# digital-psu.net
KiCad netlist of a schematic drawn in EAGLE
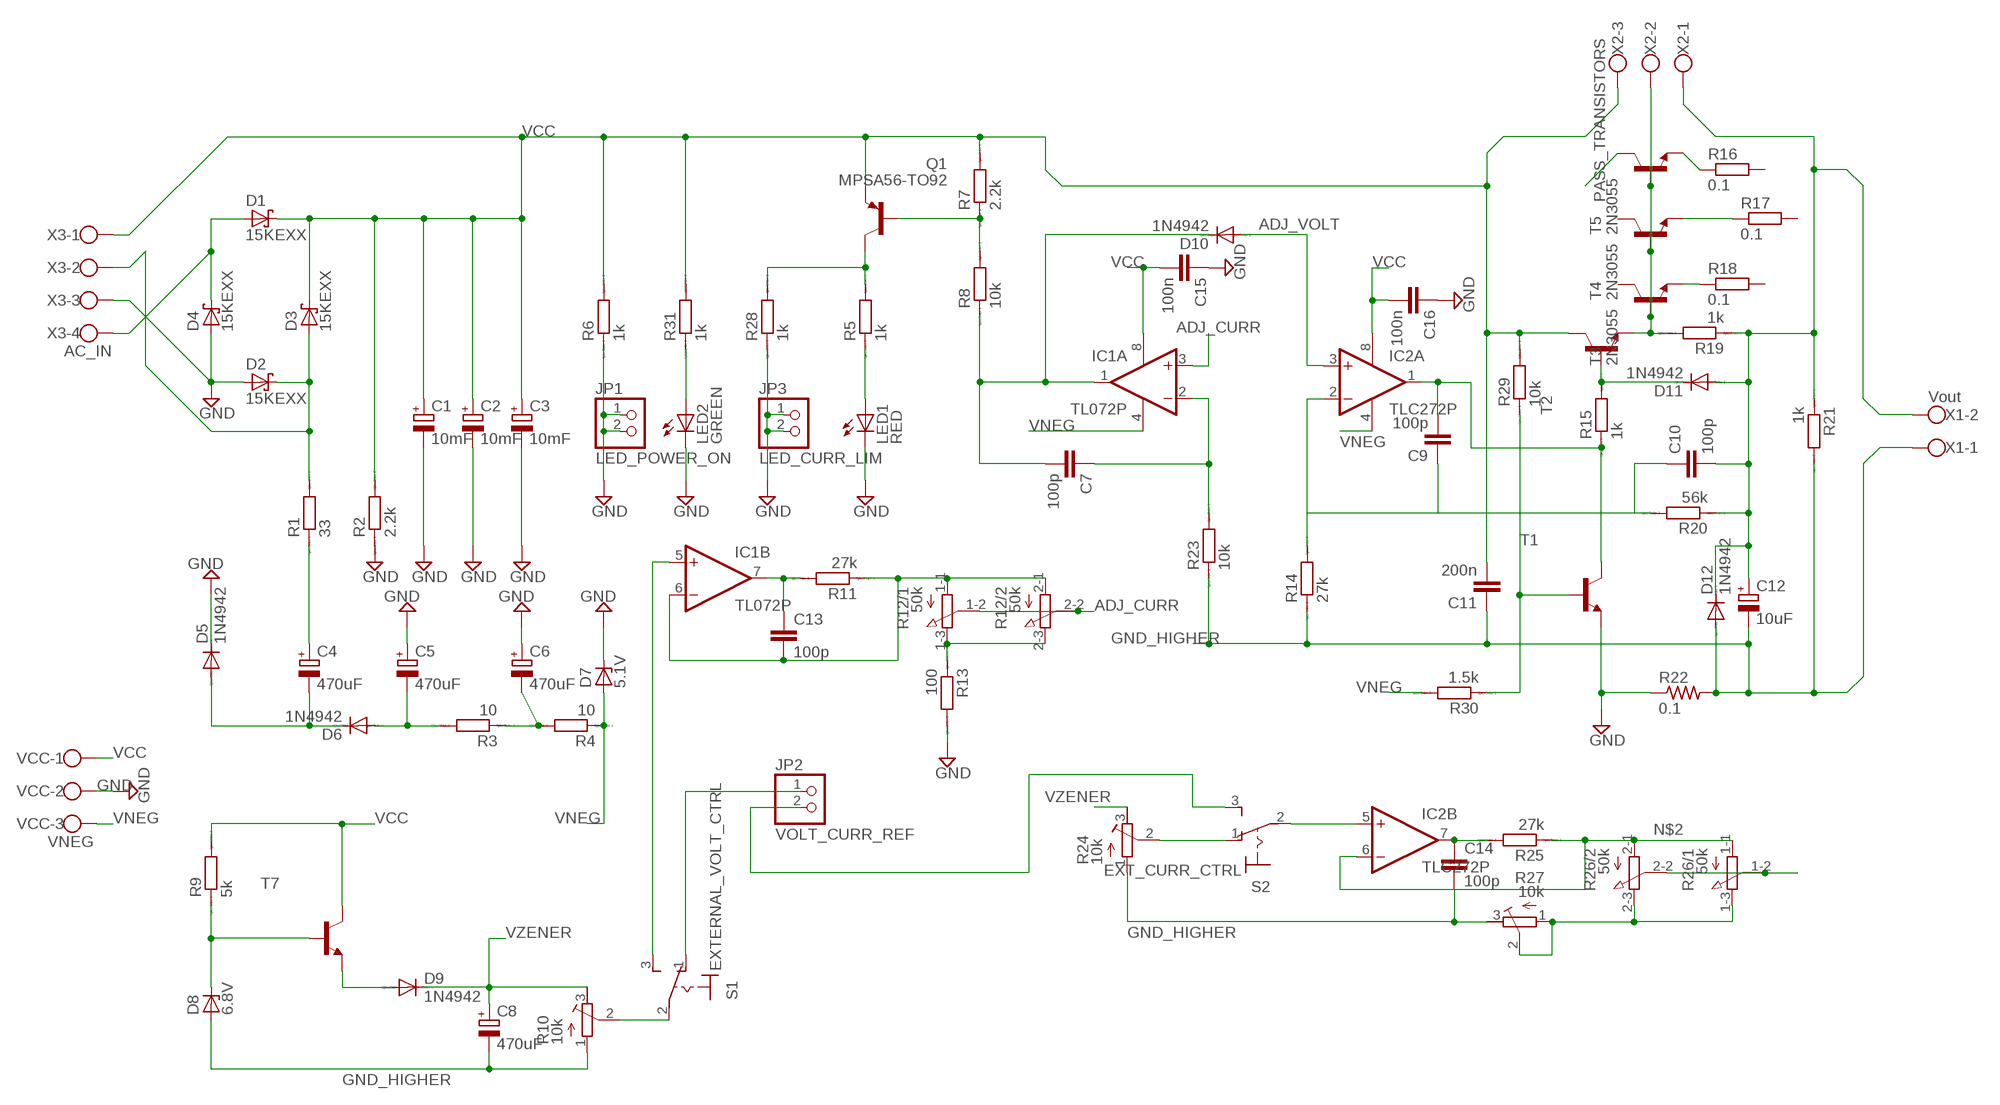
[diagram p0: schematic, sheet 1]

(export (version "E")
  (design (tool "Eeschema 10.0.6"))
  (components
    (comp (ref "C1")
      (value "10mF")
      (footprint "eagle-import:EB22,5D")
      (libsource (lib "eagle-import") (part "CPOL-EUE10-22.5"))
    )
    (comp (ref "C2")
      (value "10mF")
      (footprint "eagle-import:EB22,5D")
      (libsource (lib "eagle-import") (part "CPOL-EUE10-22.5"))
    )
    (comp (ref "C3")
      (value "10mF")
      (footprint "eagle-import:EB22,5D")
      (libsource (lib "eagle-import") (part "CPOL-EUE10-22.5"))
    )
    (comp (ref "C4")
      (value "470uF")
      (footprint "eagle-import:E5-10,5")
      (libsource (lib "eagle-import") (part "CPOL-EUE5-10.5"))
    )
    (comp (ref "C5")
      (value "470uF")
      (footprint "eagle-import:E5-10,5")
      (libsource (lib "eagle-import") (part "CPOL-EUE5-10.5"))
    )
    (comp (ref "C6")
      (value "470uF")
      (footprint "eagle-import:E5-10,5")
      (libsource (lib "eagle-import") (part "CPOL-EUE5-10.5"))
    )
    (comp (ref "C7")
      (value "100p")
      (footprint "eagle-import:C0805")
      (libsource (lib "eagle-import") (part "C-EUC0805"))
    )
    (comp (ref "C8")
      (value "470uF")
      (footprint "eagle-import:E5-10,5")
      (libsource (lib "eagle-import") (part "CPOL-EUE5-10.5"))
    )
    (comp (ref "C9")
      (value "100p")
      (footprint "eagle-import:C0805")
      (libsource (lib "eagle-import") (part "C-EUC0805"))
    )
    (comp (ref "C10")
      (value "100p")
      (footprint "eagle-import:C0805")
      (libsource (lib "eagle-import") (part "C-EUC0805"))
    )
    (comp (ref "C11")
      (value "200n")
      (footprint "eagle-import:C0805")
      (libsource (lib "eagle-import") (part "C-EUC0805"))
    )
    (comp (ref "C12")
      (value "10uF")
      (footprint "eagle-import:E5-10,5")
      (libsource (lib "eagle-import") (part "CPOL-EUE5-10.5"))
    )
    (comp (ref "C13")
      (value "100p")
      (footprint "eagle-import:C0805")
      (libsource (lib "eagle-import") (part "C-EUC0805"))
    )
    (comp (ref "C14")
      (value "100p")
      (footprint "eagle-import:C0805")
      (libsource (lib "eagle-import") (part "C-EUC0805"))
    )
    (comp (ref "C15")
      (value "100n")
      (footprint "eagle-import:C0805")
      (libsource (lib "eagle-import") (part "C-EUC0805"))
    )
    (comp (ref "C16")
      (value "100n")
      (footprint "eagle-import:C0805")
      (libsource (lib "eagle-import") (part "C-EUC0805"))
    )
    (comp (ref "D1")
      (value "15KEXX")
      (footprint "eagle-import:CB429-17")
      (libsource (lib "eagle-import") (part "15KEXX"))
    )
    (comp (ref "D2")
      (value "15KEXX")
      (footprint "eagle-import:CB429-17")
      (libsource (lib "eagle-import") (part "15KEXX"))
    )
    (comp (ref "D3")
      (value "15KEXX")
      (footprint "eagle-import:CB429-17")
      (libsource (lib "eagle-import") (part "15KEXX"))
    )
    (comp (ref "D4")
      (value "15KEXX")
      (footprint "eagle-import:CB429-17")
      (libsource (lib "eagle-import") (part "15KEXX"))
    )
    (comp (ref "D5")
      (value "1N4942")
      (footprint "eagle-import:DO41-10")
      (libsource (lib "eagle-import") (part "1N4942"))
    )
    (comp (ref "D6")
      (value "1N4942")
      (footprint "eagle-import:DO41-10")
      (libsource (lib "eagle-import") (part "1N4942"))
    )
    (comp (ref "D7")
      (value "5.1V")
      (footprint "eagle-import:C1702-15")
      (libsource (lib "eagle-import") (part "ZENER-DIODEC1702-15"))
    )
    (comp (ref "D8")
      (value "6.8V")
      (footprint "eagle-import:C1702-15")
      (libsource (lib "eagle-import") (part "ZENER-DIODEC1702-15"))
    )
    (comp (ref "D9")
      (value "1N4942")
      (footprint "eagle-import:DO41-10")
      (libsource (lib "eagle-import") (part "1N4942"))
    )
    (comp (ref "D10")
      (value "1N4942")
      (footprint "eagle-import:DO41-10")
      (libsource (lib "eagle-import") (part "1N4942"))
    )
    (comp (ref "D11")
      (value "1N4942")
      (footprint "eagle-import:DO41-10")
      (libsource (lib "eagle-import") (part "1N4942"))
    )
    (comp (ref "D12")
      (value "1N4942")
      (footprint "eagle-import:DO41-10")
      (libsource (lib "eagle-import") (part "1N4942"))
    )
    (comp (ref "IC1")
      (value "TL072P")
      (footprint "eagle-import:DIL08")
      (libsource (lib "eagle-import") (part "TL072P"))
    )
    (comp (ref "IC2")
      (value "TLC272P")
      (footprint "eagle-import:DIL08")
      (libsource (lib "eagle-import") (part "TLC272P"))
    )
    (comp (ref "JP1")
      (value "LED_POWER_ON")
      (footprint "eagle-import:1X02")
      (libsource (lib "eagle-import") (part "PINHD-1X2"))
    )
    (comp (ref "JP2")
      (value "VOLT_CURR_REF")
      (footprint "eagle-import:1X02")
      (libsource (lib "eagle-import") (part "PINHD-1X2"))
    )
    (comp (ref "JP3")
      (value "LED_CURR_LIM")
      (footprint "eagle-import:1X02")
      (libsource (lib "eagle-import") (part "PINHD-1X2"))
    )
    (comp (ref "LED1")
      (value "RED")
      (footprint "eagle-import:LED5MM")
      (libsource (lib "eagle-import") (part "LED5MM"))
    )
    (comp (ref "LED2")
      (value "GREEN")
      (footprint "eagle-import:LED5MM")
      (libsource (lib "eagle-import") (part "LED5MM"))
    )
    (comp (ref "Q1")
      (value "MPSA56-TO92")
      (footprint "eagle-import:TO92-CBE")
      (libsource (lib "eagle-import") (part "-?TO92MPSA56"))
    )
    (comp (ref "R1")
      (value "33")
      (footprint "eagle-import:R0805")
      (libsource (lib "eagle-import") (part "R"))
    )
    (comp (ref "R2")
      (value "2.2k")
      (footprint "eagle-import:R0805")
      (libsource (lib "eagle-import") (part "R"))
    )
    (comp (ref "R3")
      (value "10")
      (footprint "eagle-import:R0805")
      (libsource (lib "eagle-import") (part "R"))
    )
    (comp (ref "R4")
      (value "10")
      (footprint "eagle-import:R0805")
      (libsource (lib "eagle-import") (part "R"))
    )
    (comp (ref "R5")
      (value "1k")
      (footprint "eagle-import:R0805")
      (libsource (lib "eagle-import") (part "R"))
    )
    (comp (ref "R6")
      (value "1k")
      (footprint "eagle-import:R0805")
      (libsource (lib "eagle-import") (part "R"))
    )
    (comp (ref "R7")
      (value "2.2k")
      (footprint "eagle-import:R0805")
      (libsource (lib "eagle-import") (part "R"))
    )
    (comp (ref "R8")
      (value "10k")
      (footprint "eagle-import:R0805")
      (libsource (lib "eagle-import") (part "R"))
    )
    (comp (ref "R9")
      (value "5k")
      (footprint "eagle-import:R0805")
      (libsource (lib "eagle-import") (part "R"))
    )
    (comp (ref "R10")
      (value "10k")
      (footprint "eagle-import:RTRIM64W")
      (libsource (lib "eagle-import") (part "R-TRIMM64W"))
    )
    (comp (ref "R11")
      (value "27k")
      (footprint "eagle-import:R0805")
      (libsource (lib "eagle-import") (part "R"))
    )
    (comp (ref "R12")
      (value "50k")
      (footprint "eagle-import:3RP_1610G")
      (libsource (lib "eagle-import") (part "3RP/1610G"))
    )
    (comp (ref "R13")
      (value "100")
      (footprint "eagle-import:R0805")
      (libsource (lib "eagle-import") (part "R"))
    )
    (comp (ref "R14")
      (value "27k")
      (footprint "eagle-import:R0805")
      (libsource (lib "eagle-import") (part "R"))
    )
    (comp (ref "R15")
      (value "1k")
      (footprint "eagle-import:R0805")
      (libsource (lib "eagle-import") (part "R"))
    )
    (comp (ref "R16")
      (value "0.1")
      (footprint "eagle-import:VTA55")
      (libsource (lib "eagle-import") (part "R-EU_VTA55"))
    )
    (comp (ref "R17")
      (value "0.1")
      (footprint "eagle-import:VTA55")
      (libsource (lib "eagle-import") (part "R-EU_VTA55"))
    )
    (comp (ref "R18")
      (value "0.1")
      (footprint "eagle-import:VTA55")
      (libsource (lib "eagle-import") (part "R-EU_VTA55"))
    )
    (comp (ref "R19")
      (value "1k")
      (footprint "eagle-import:R0805")
      (libsource (lib "eagle-import") (part "R"))
    )
    (comp (ref "R20")
      (value "56k")
      (footprint "eagle-import:R0805")
      (libsource (lib "eagle-import") (part "R"))
    )
    (comp (ref "R21")
      (value "1k")
      (footprint "eagle-import:R0805")
      (libsource (lib "eagle-import") (part "R"))
    )
    (comp (ref "R22")
      (value "0.1")
      (footprint "eagle-import:VTA52")
      (libsource (lib "eagle-import") (part "R-US_VTA52"))
    )
    (comp (ref "R23")
      (value "10k")
      (footprint "eagle-import:R0805")
      (libsource (lib "eagle-import") (part "R"))
    )
    (comp (ref "R24")
      (value "10k")
      (footprint "eagle-import:RTRIM64W")
      (libsource (lib "eagle-import") (part "R-TRIMM64W"))
    )
    (comp (ref "R25")
      (value "27k")
      (footprint "eagle-import:R0805")
      (libsource (lib "eagle-import") (part "R"))
    )
    (comp (ref "R26")
      (value "50k")
      (footprint "eagle-import:3RP_1610G")
      (libsource (lib "eagle-import") (part "3RP/1610G"))
    )
    (comp (ref "R27")
      (value "10k")
      (footprint "eagle-import:RTRIM64W")
      (libsource (lib "eagle-import") (part "R-TRIMM64W"))
    )
    (comp (ref "R28")
      (value "1k")
      (footprint "eagle-import:R0805")
      (libsource (lib "eagle-import") (part "R"))
    )
    (comp (ref "R29")
      (value "10k")
      (footprint "eagle-import:R0805")
      (libsource (lib "eagle-import") (part "R"))
    )
    (comp (ref "R30")
      (value "1.5k")
      (footprint "eagle-import:R0805")
      (libsource (lib "eagle-import") (part "R"))
    )
    (comp (ref "R31")
      (value "1k")
      (footprint "eagle-import:R0805")
      (libsource (lib "eagle-import") (part "R"))
    )
    (comp (ref "S1")
      (value "EXTERNAL_VOLT_CTRL")
      (footprint "eagle-import:320-916")
      (libsource (lib "eagle-import") (part "320-916"))
    )
    (comp (ref "S2")
      (value "EXT_CURR_CTRL")
      (footprint "eagle-import:320-916")
      (libsource (lib "eagle-import") (part "320-916"))
    )
    (comp (ref "T1")
      (value "-NPN-TO92-EBC")
      (footprint "eagle-import:TO92-EBC")
      (libsource (lib "eagle-import") (part "-NPN-TO92-EBC"))
    )
    (comp (ref "T2")
      (value "-NPN-TO92-EBC")
      (footprint "eagle-import:TO92-EBC")
      (libsource (lib "eagle-import") (part "-NPN-TO92-EBC"))
    )
    (comp (ref "T3")
      (value "2N3055")
      (footprint "eagle-import:TO3")
      (libsource (lib "eagle-import") (part "-NPN-TO3/"))
    )
    (comp (ref "T4")
      (value "2N3055")
      (footprint "eagle-import:TO3")
      (libsource (lib "eagle-import") (part "-NPN-TO3/"))
    )
    (comp (ref "T5")
      (value "2N3055")
      (footprint "eagle-import:TO3")
      (libsource (lib "eagle-import") (part "-NPN-TO3/"))
    )
    (comp (ref "T7")
      (value "-NPN-TO92-EBC")
      (footprint "eagle-import:TO92-EBC")
      (libsource (lib "eagle-import") (part "-NPN-TO92-EBC"))
    )
    (comp (ref "VCC")
      (value "VNEG")
      (footprint "eagle-import:W237-103")
      (fields (field (name "MPN") "237-103"))
      (libsource (lib "eagle-import") (part "W237-103"))
    )
    (comp (ref "X1")
      (value "Vout")
      (footprint "eagle-import:W237-113")
      (libsource (lib "eagle-import") (part "W237-113"))
    )
    (comp (ref "X2")
      (value "PASS_TRANSISTORS")
      (footprint "eagle-import:W237-103")
      (fields (field (name "MPN") "237-103"))
      (libsource (lib "eagle-import") (part "W237-103"))
    )
    (comp (ref "X3")
      (value "AC_IN")
      (footprint "eagle-import:W237-4")
      (libsource (lib "eagle-import") (part "W237-4"))
    )
  )
  (nets
    (net (code "1") (name "/ADJ_CURR") (class "Default")
      (node (ref "IC1") (pin "3") (pinfunction "+IN_3") (pintype "input"))
      (node (ref "R12") (pin "1-2") (pinfunction "S_1-2") (pintype "passive"))
      (node (ref "R12") (pin "2-2") (pinfunction "S_2-2") (pintype "passive"))
    )
    (net (code "2") (name "/ADJ_VOLT") (class "Default")
      (node (ref "D10") (pin "A") (pinfunction "A_A") (pintype "passive"))
      (node (ref "IC2") (pin "3") (pinfunction "+IN_3") (pintype "input"))
      (node (ref "R26") (pin "1-2") (pinfunction "S_1-2") (pintype "passive"))
      (node (ref "R26") (pin "2-2") (pinfunction "S_2-2") (pintype "passive"))
    )
    (net (code "3") (name "/GND_HIGHER") (class "Default")
      (node (ref "C11") (pin "1") (pinfunction "1_1") (pintype "passive"))
      (node (ref "C12") (pin "-") (pinfunction "-_-") (pintype "passive"))
      (node (ref "C14") (pin "2") (pinfunction "2_2") (pintype "passive"))
      (node (ref "C8") (pin "-") (pinfunction "-_-") (pintype "passive"))
      (node (ref "D12") (pin "A") (pinfunction "A_A") (pintype "passive"))
      (node (ref "D8") (pin "A") (pinfunction "A_A") (pintype "passive"))
      (node (ref "R10") (pin "1") (pinfunction "A_1") (pintype "passive"))
      (node (ref "R14") (pin "1") (pinfunction "1_1") (pintype "passive"))
      (node (ref "R21") (pin "2") (pinfunction "2_2") (pintype "passive"))
      (node (ref "R22") (pin "2") (pinfunction "2_2") (pintype "passive"))
      (node (ref "R23") (pin "1") (pinfunction "1_1") (pintype "passive"))
      (node (ref "R24") (pin "1") (pinfunction "A_1") (pintype "passive"))
      (node (ref "R27") (pin "3") (pinfunction "E_3") (pintype "passive"))
      (node (ref "X1") (pin "1") (pinfunction "KL_1") (pintype "passive"))
    )
    (net (code "4") (name "/N$2") (class "Default")
      (node (ref "IC2") (pin "6") (pinfunction "-IN_6") (pintype "input"))
      (node (ref "R25") (pin "1") (pinfunction "1_1") (pintype "passive"))
      (node (ref "R26") (pin "1-1") (pinfunction "A_1-1") (pintype "passive"))
      (node (ref "R26") (pin "2-1") (pinfunction "A_2-1") (pintype "passive"))
    )
    (net (code "5") (name "/VCC") (class "Default")
      (node (ref "C1") (pin "+") (pinfunction "+_+") (pintype "passive"))
      (node (ref "C11") (pin "2") (pinfunction "2_2") (pintype "passive"))
      (node (ref "C15") (pin "2") (pinfunction "2_2") (pintype "passive"))
      (node (ref "C16") (pin "2") (pinfunction "2_2") (pintype "passive"))
      (node (ref "C2") (pin "+") (pinfunction "+_+") (pintype "passive"))
      (node (ref "C3") (pin "+") (pinfunction "+_+") (pintype "passive"))
      (node (ref "D1") (pin "C") (pinfunction "C_C") (pintype "passive"))
      (node (ref "D3") (pin "C") (pinfunction "C_C") (pintype "passive"))
      (node (ref "IC1") (pin "8") (pinfunction "V+_8") (pintype "power_in"))
      (node (ref "IC2") (pin "8") (pinfunction "V+_8") (pintype "power_in"))
      (node (ref "Q1") (pin "E") (pinfunction "E_E") (pintype "passive"))
      (node (ref "R2") (pin "2") (pinfunction "2_2") (pintype "passive"))
      (node (ref "R29") (pin "2") (pinfunction "2_2") (pintype "passive"))
      (node (ref "R31") (pin "2") (pinfunction "2_2") (pintype "passive"))
      (node (ref "R6") (pin "2") (pinfunction "2_2") (pintype "passive"))
      (node (ref "R7") (pin "2") (pinfunction "2_2") (pintype "passive"))
      (node (ref "R9") (pin "2") (pinfunction "2_2") (pintype "passive"))
      (node (ref "T2") (pin "C") (pinfunction "C_C") (pintype "passive"))
      (node (ref "T7") (pin "C") (pinfunction "C_C") (pintype "passive"))
      (node (ref "VCC") (pin "1") (pinfunction "KL_1") (pintype "passive"))
      (node (ref "X2") (pin "3") (pinfunction "KL_3") (pintype "passive"))
      (node (ref "X3") (pin "1") (pinfunction "KL_1") (pintype "passive"))
    )
    (net (code "6") (name "/VNEG") (class "Default")
      (node (ref "D7") (pin "A") (pinfunction "A_A") (pintype "passive"))
      (node (ref "IC1") (pin "4") (pinfunction "V-_4") (pintype "power_in"))
      (node (ref "IC2") (pin "4") (pinfunction "V-_4") (pintype "power_in"))
      (node (ref "R30") (pin "2") (pinfunction "2_2") (pintype "passive"))
      (node (ref "R4") (pin "1") (pinfunction "1_1") (pintype "passive"))
      (node (ref "VCC") (pin "3") (pinfunction "KL_3") (pintype "passive"))
    )
    (net (code "7") (name "/VZENER") (class "Default")
      (node (ref "C8") (pin "+") (pinfunction "+_+") (pintype "passive"))
      (node (ref "D9") (pin "C") (pinfunction "C_C") (pintype "passive"))
      (node (ref "R10") (pin "3") (pinfunction "E_3") (pintype "passive"))
      (node (ref "R24") (pin "3") (pinfunction "E_3") (pintype "passive"))
    )
    (net (code "8") (name "GND") (class "Default")
      (node (ref "C1") (pin "-") (pinfunction "-_-") (pintype "passive"))
      (node (ref "C15") (pin "1") (pinfunction "1_1") (pintype "passive"))
      (node (ref "C16") (pin "1") (pinfunction "1_1") (pintype "passive"))
      (node (ref "C2") (pin "-") (pinfunction "-_-") (pintype "passive"))
      (node (ref "C3") (pin "-") (pinfunction "-_-") (pintype "passive"))
      (node (ref "C5") (pin "+") (pinfunction "+_+") (pintype "passive"))
      (node (ref "C6") (pin "+") (pinfunction "+_+") (pintype "passive"))
      (node (ref "D2") (pin "A") (pinfunction "A_A") (pintype "passive"))
      (node (ref "D4") (pin "A") (pinfunction "A_A") (pintype "passive"))
      (node (ref "D5") (pin "C") (pinfunction "C_C") (pintype "passive"))
      (node (ref "D7") (pin "C") (pinfunction "C_C") (pintype "passive"))
      (node (ref "JP1") (pin "1") (pinfunction "1_1") (pintype "passive"))
      (node (ref "JP1") (pin "2") (pinfunction "2_2") (pintype "passive"))
      (node (ref "JP3") (pin "1") (pinfunction "1_1") (pintype "passive"))
      (node (ref "JP3") (pin "2") (pinfunction "2_2") (pintype "passive"))
      (node (ref "LED1") (pin "K") (pinfunction "C_K") (pintype "passive"))
      (node (ref "LED2") (pin "K") (pinfunction "C_K") (pintype "passive"))
      (node (ref "R13") (pin "2") (pinfunction "2_2") (pintype "passive"))
      (node (ref "R2") (pin "1") (pinfunction "1_1") (pintype "passive"))
      (node (ref "R22") (pin "1") (pinfunction "1_1") (pintype "passive"))
      (node (ref "R28") (pin "1") (pinfunction "1_1") (pintype "passive"))
      (node (ref "R6") (pin "1") (pinfunction "1_1") (pintype "passive"))
      (node (ref "T1") (pin "E") (pinfunction "E_E") (pintype "passive"))
      (node (ref "VCC") (pin "2") (pinfunction "KL_2") (pintype "passive"))
      (node (ref "X3") (pin "3") (pinfunction "KL_3") (pintype "passive"))
    )
    (net (code "9") (name "Net-(C4-Pad+)") (class "Default")
      (node (ref "C4") (pin "+") (pinfunction "+_+") (pintype "passive"))
      (node (ref "R1") (pin "1") (pinfunction "1_1") (pintype "passive"))
    )
    (net (code "10") (name "Net-(C4-Pad-)") (class "Default")
      (node (ref "C4") (pin "-") (pinfunction "-_-") (pintype "passive"))
      (node (ref "D5") (pin "A") (pinfunction "A_A") (pintype "passive"))
      (node (ref "D6") (pin "C") (pinfunction "C_C") (pintype "passive"))
    )
    (net (code "11") (name "Net-(C5-Pad-)") (class "Default")
      (node (ref "C5") (pin "-") (pinfunction "-_-") (pintype "passive"))
      (node (ref "D6") (pin "A") (pinfunction "A_A") (pintype "passive"))
      (node (ref "R3") (pin "2") (pinfunction "2_2") (pintype "passive"))
    )
    (net (code "12") (name "Net-(C6-Pad-)") (class "Default")
      (node (ref "C6") (pin "-") (pinfunction "-_-") (pintype "passive"))
      (node (ref "R3") (pin "1") (pinfunction "1_1") (pintype "passive"))
      (node (ref "R4") (pin "2") (pinfunction "2_2") (pintype "passive"))
    )
    (net (code "13") (name "Net-(D8-PadC)") (class "Default")
      (node (ref "D8") (pin "C") (pinfunction "C_C") (pintype "passive"))
      (node (ref "R9") (pin "1") (pinfunction "1_1") (pintype "passive"))
      (node (ref "T7") (pin "B") (pinfunction "B_B") (pintype "passive"))
    )
    (net (code "14") (name "Net-(D9-PadA)") (class "Default")
      (node (ref "D9") (pin "A") (pinfunction "A_A") (pintype "passive"))
      (node (ref "T7") (pin "E") (pinfunction "E_E") (pintype "passive"))
    )
    (net (code "15") (name "Net-(D11-PadC)") (class "Default")
      (node (ref "D11") (pin "C") (pinfunction "C_C") (pintype "passive"))
      (node (ref "R15") (pin "2") (pinfunction "2_2") (pintype "passive"))
      (node (ref "T2") (pin "B") (pinfunction "B_B") (pintype "passive"))
    )
    (net (code "16") (name "Net-(IC1A--IN)") (class "Default")
      (node (ref "C7") (pin "1") (pinfunction "1_1") (pintype "passive"))
      (node (ref "IC1") (pin "2") (pinfunction "-IN_2") (pintype "input"))
      (node (ref "R23") (pin "2") (pinfunction "2_2") (pintype "passive"))
    )
    (net (code "17") (name "Net-(IC1A-OUT)") (class "Default")
      (node (ref "C7") (pin "2") (pinfunction "2_2") (pintype "passive"))
      (node (ref "D10") (pin "C") (pinfunction "C_C") (pintype "passive"))
      (node (ref "IC1") (pin "1") (pinfunction "OUT_1") (pintype "output"))
      (node (ref "R8") (pin "1") (pinfunction "1_1") (pintype "passive"))
    )
    (net (code "18") (name "Net-(IC1B-+IN)") (class "Default")
      (node (ref "IC1") (pin "5") (pinfunction "+IN_5") (pintype "input"))
      (node (ref "S1") (pin "3") (pinfunction "S_3") (pintype "passive"))
    )
    (net (code "19") (name "Net-(IC1B--IN)") (class "Default")
      (node (ref "C13") (pin "2") (pinfunction "2_2") (pintype "passive"))
      (node (ref "IC1") (pin "6") (pinfunction "-IN_6") (pintype "input"))
      (node (ref "R11") (pin "1") (pinfunction "1_1") (pintype "passive"))
      (node (ref "R12") (pin "1-1") (pinfunction "A_1-1") (pintype "passive"))
      (node (ref "R12") (pin "2-1") (pinfunction "A_2-1") (pintype "passive"))
    )
    (net (code "20") (name "Net-(IC1B-OUT)") (class "Default")
      (node (ref "C13") (pin "1") (pinfunction "1_1") (pintype "passive"))
      (node (ref "IC1") (pin "7") (pinfunction "OUT_7") (pintype "output"))
      (node (ref "R11") (pin "2") (pinfunction "2_2") (pintype "passive"))
    )
    (net (code "21") (name "Net-(IC2A--IN)") (class "Default")
      (node (ref "C10") (pin "1") (pinfunction "1_1") (pintype "passive"))
      (node (ref "C9") (pin "1") (pinfunction "1_1") (pintype "passive"))
      (node (ref "IC2") (pin "2") (pinfunction "-IN_2") (pintype "input"))
      (node (ref "R14") (pin "2") (pinfunction "2_2") (pintype "passive"))
      (node (ref "R20") (pin "2") (pinfunction "2_2") (pintype "passive"))
    )
    (net (code "22") (name "Net-(IC2A-OUT)") (class "Default")
      (node (ref "C9") (pin "2") (pinfunction "2_2") (pintype "passive"))
      (node (ref "IC2") (pin "1") (pinfunction "OUT_1") (pintype "output"))
      (node (ref "R15") (pin "1") (pinfunction "1_1") (pintype "passive"))
      (node (ref "T1") (pin "C") (pinfunction "C_C") (pintype "passive"))
    )
    (net (code "23") (name "Net-(IC2B-+IN)") (class "Default")
      (node (ref "IC2") (pin "5") (pinfunction "+IN_5") (pintype "input"))
      (node (ref "S2") (pin "2") (pinfunction "P_2") (pintype "passive"))
    )
    (net (code "24") (name "Net-(IC2B-OUT)") (class "Default")
      (node (ref "C14") (pin "1") (pinfunction "1_1") (pintype "passive"))
      (node (ref "IC2") (pin "7") (pinfunction "OUT_7") (pintype "output"))
      (node (ref "R25") (pin "2") (pinfunction "2_2") (pintype "passive"))
    )
    (net (code "25") (name "Net-(LED1-PadA)") (class "Default")
      (node (ref "LED1") (pin "A") (pinfunction "A_A") (pintype "passive"))
      (node (ref "R5") (pin "1") (pinfunction "1_1") (pintype "passive"))
    )
    (net (code "26") (name "Net-(LED2-PadA)") (class "Default")
      (node (ref "LED2") (pin "A") (pinfunction "A_A") (pintype "passive"))
      (node (ref "R31") (pin "1") (pinfunction "1_1") (pintype "passive"))
    )
    (net (code "27") (name "Net-(Q1-PadB)") (class "Default")
      (node (ref "Q1") (pin "B") (pinfunction "B_B") (pintype "passive"))
      (node (ref "R7") (pin "1") (pinfunction "1_1") (pintype "passive"))
      (node (ref "R8") (pin "2") (pinfunction "2_2") (pintype "passive"))
    )
    (net (code "28") (name "Net-(Q1-PadC)") (class "Default")
      (node (ref "Q1") (pin "C") (pinfunction "C_C") (pintype "passive"))
      (node (ref "R28") (pin "2") (pinfunction "2_2") (pintype "passive"))
      (node (ref "R5") (pin "2") (pinfunction "2_2") (pintype "passive"))
    )
    (net (code "29") (name "Net-(R10-S)") (class "Default")
      (node (ref "R10") (pin "2") (pinfunction "S_2") (pintype "passive"))
      (node (ref "S1") (pin "2") (pinfunction "P_2") (pintype "passive"))
    )
    (net (code "30") (name "Net-(R12A-E)") (class "Default")
      (node (ref "R12") (pin "1-3") (pinfunction "E_1-3") (pintype "passive"))
      (node (ref "R12") (pin "2-3") (pinfunction "E_2-3") (pintype "passive"))
      (node (ref "R13") (pin "1") (pinfunction "1_1") (pintype "passive"))
    )
    (net (code "31") (name "Net-(R16-Pad1)") (class "Default")
      (node (ref "R16") (pin "1") (pinfunction "1_1") (pintype "passive"))
      (node (ref "T5") (pin "E") (pinfunction "E_E") (pintype "passive"))
    )
    (net (code "32") (name "Net-(R17-Pad1)") (class "Default")
      (node (ref "R17") (pin "1") (pinfunction "1_1") (pintype "passive"))
      (node (ref "T4") (pin "E") (pinfunction "E_E") (pintype "passive"))
    )
    (net (code "33") (name "Net-(R18-Pad1)") (class "Default")
      (node (ref "R18") (pin "1") (pinfunction "1_1") (pintype "passive"))
      (node (ref "T3") (pin "E") (pinfunction "E_E") (pintype "passive"))
    )
    (net (code "34") (name "Net-(R24-S)") (class "Default")
      (node (ref "R24") (pin "2") (pinfunction "S_2") (pintype "passive"))
      (node (ref "S2") (pin "1") (pinfunction "O_1") (pintype "passive"))
    )
    (net (code "35") (name "Net-(R26A-E)") (class "Default")
      (node (ref "R26") (pin "1-3") (pinfunction "E_1-3") (pintype "passive"))
      (node (ref "R26") (pin "2-3") (pinfunction "E_2-3") (pintype "passive"))
      (node (ref "R27") (pin "1") (pinfunction "A_1") (pintype "passive"))
      (node (ref "R27") (pin "2") (pinfunction "S_2") (pintype "passive"))
    )
    (net (code "36") (name "Net-(R29-Pad1)") (class "Default")
      (node (ref "R29") (pin "1") (pinfunction "1_1") (pintype "passive"))
      (node (ref "R30") (pin "1") (pinfunction "1_1") (pintype "passive"))
      (node (ref "T1") (pin "B") (pinfunction "B_B") (pintype "passive"))
    )
    (net (code "37") (name "Net-(S1-O)") (class "Default")
      (node (ref "JP2") (pin "1") (pinfunction "1_1") (pintype "passive"))
      (node (ref "S1") (pin "1") (pinfunction "O_1") (pintype "passive"))
    )
    (net (code "38") (name "Net-(S2-S)") (class "Default")
      (node (ref "JP2") (pin "2") (pinfunction "2_2") (pintype "passive"))
      (node (ref "S2") (pin "3") (pinfunction "S_3") (pintype "passive"))
    )
    (net (code "39") (name "Net-(X1B-KL)") (class "Default")
      (node (ref "C10") (pin "2") (pinfunction "2_2") (pintype "passive"))
      (node (ref "C12") (pin "+") (pinfunction "+_+") (pintype "passive"))
      (node (ref "D11") (pin "A") (pinfunction "A_A") (pintype "passive"))
      (node (ref "D12") (pin "C") (pinfunction "C_C") (pintype "passive"))
      (node (ref "R19") (pin "1") (pinfunction "1_1") (pintype "passive"))
      (node (ref "R20") (pin "1") (pinfunction "1_1") (pintype "passive"))
      (node (ref "R21") (pin "1") (pinfunction "1_1") (pintype "passive"))
      (node (ref "X1") (pin "2") (pinfunction "KL_2") (pintype "passive"))
      (node (ref "X2") (pin "1") (pinfunction "KL_1") (pintype "passive"))
    )
    (net (code "40") (name "Net-(X2B-KL)") (class "Default")
      (node (ref "R19") (pin "2") (pinfunction "2_2") (pintype "passive"))
      (node (ref "T2") (pin "E") (pinfunction "E_E") (pintype "passive"))
      (node (ref "T3") (pin "B") (pinfunction "B_B") (pintype "passive"))
      (node (ref "T4") (pin "B") (pinfunction "B_B") (pintype "passive"))
      (node (ref "T5") (pin "B") (pinfunction "B_B") (pintype "passive"))
      (node (ref "X2") (pin "2") (pinfunction "KL_2") (pintype "passive"))
    )
    (net (code "41") (name "Net-(X3B-KL)") (class "Default")
      (node (ref "D2") (pin "C") (pinfunction "C_C") (pintype "passive"))
      (node (ref "D3") (pin "A") (pinfunction "A_A") (pintype "passive"))
      (node (ref "R1") (pin "2") (pinfunction "2_2") (pintype "passive"))
      (node (ref "X3") (pin "2") (pinfunction "KL_2") (pintype "passive"))
    )
    (net (code "42") (name "Net-(X3D-KL)") (class "Default")
      (node (ref "D1") (pin "A") (pinfunction "A_A") (pintype "passive"))
      (node (ref "D4") (pin "C") (pinfunction "C_C") (pintype "passive"))
      (node (ref "X3") (pin "4") (pinfunction "KL_4") (pintype "passive"))
    )
    (net (code "43") (name "unconnected-(R16-Pad2)") (class "Default")
      (node (ref "R16") (pin "2") (pinfunction "2_2") (pintype "passive"))
    )
    (net (code "44") (name "unconnected-(R17-Pad2)") (class "Default")
      (node (ref "R17") (pin "2") (pinfunction "2_2") (pintype "passive"))
    )
    (net (code "45") (name "unconnected-(R18-Pad2)") (class "Default")
      (node (ref "R18") (pin "2") (pinfunction "2_2") (pintype "passive"))
    )
    (net (code "46") (name "unconnected-(T3-PadC)") (class "Default")
      (node (ref "T3") (pin "C") (pinfunction "C_C") (pintype "passive"))
    )
    (net (code "47") (name "unconnected-(T4-PadC)") (class "Default")
      (node (ref "T4") (pin "C") (pinfunction "C_C") (pintype "passive"))
    )
    (net (code "48") (name "unconnected-(T5-PadC)") (class "Default")
      (node (ref "T5") (pin "C") (pinfunction "C_C") (pintype "passive"))
    )
  )
)
